# PCB_SIT210.net
KiCad netlist of a schematic drawn in EasyEDA
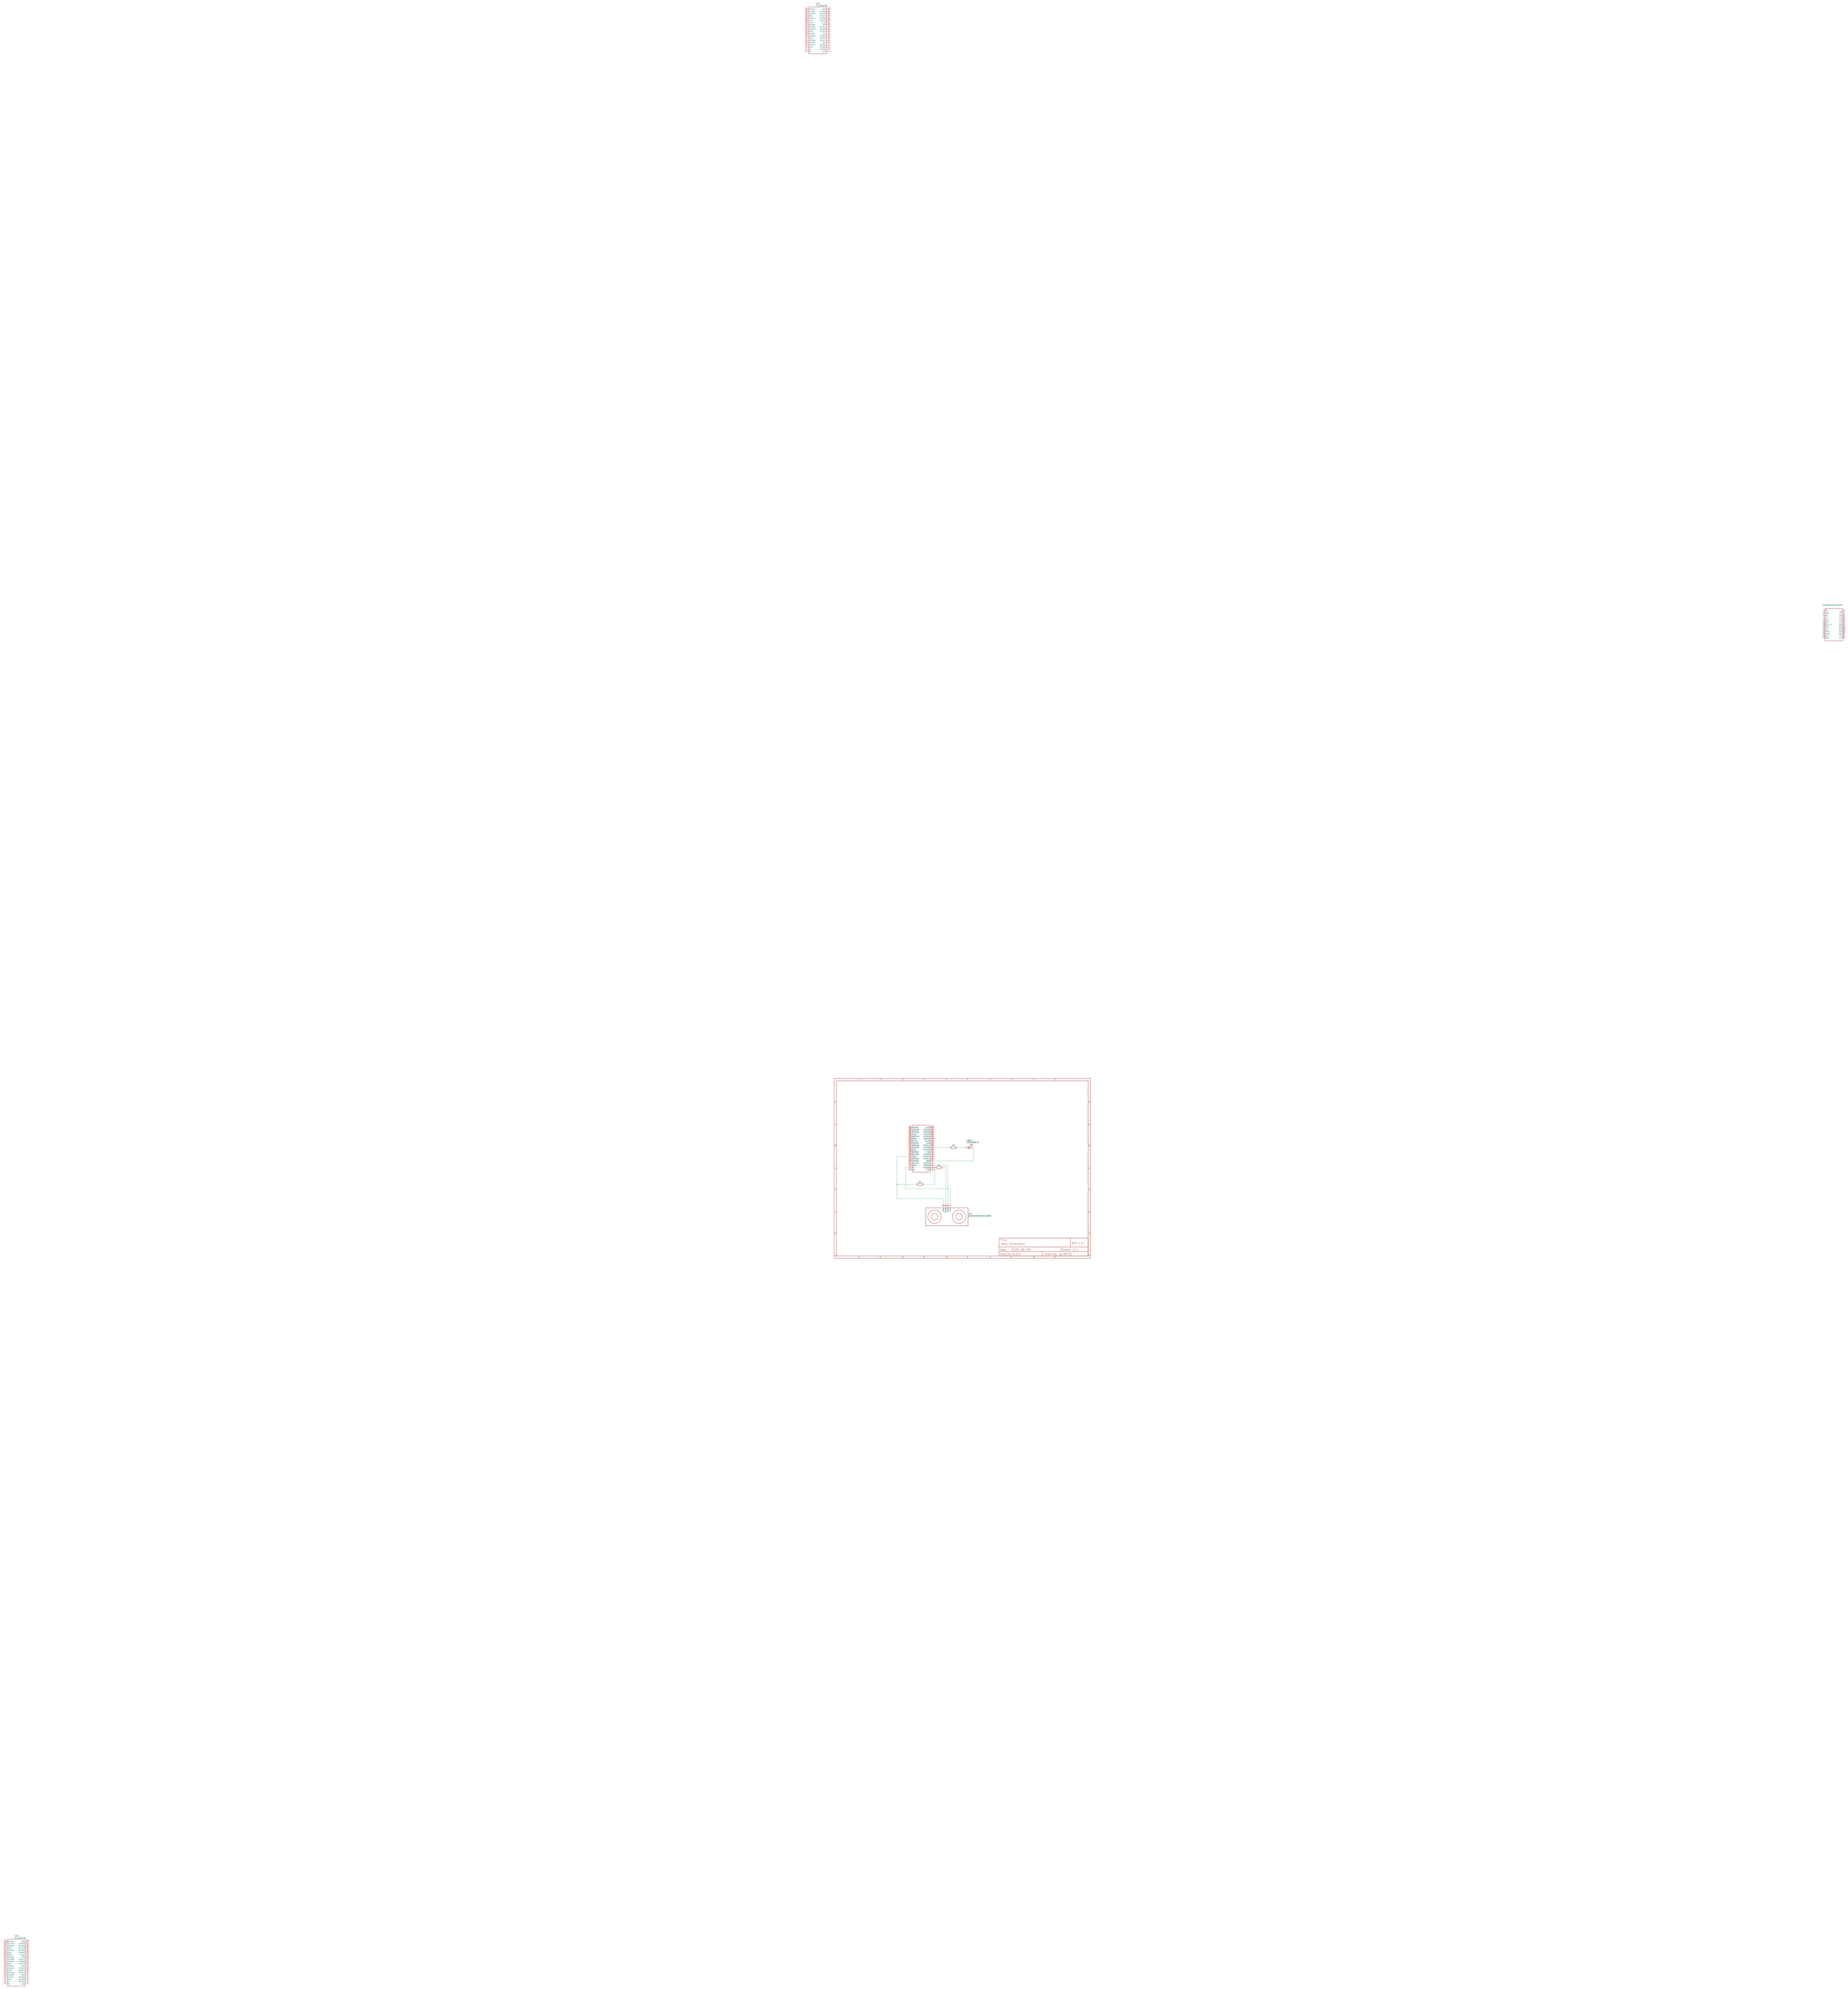
[diagram p0: schematic sheet]

(export (version "E")
  (design (tool "Eeschema 10.0.6"))
  (components
    (comp (ref "LED1")
      (value "LED-0603_R")
      (fields
        (field (name "BOM_Manufacturer Part") "19-217/R6C-AL1M2VY/3T")
        (field (name "BOM_Supplier Part") "C72044")
      )
      (libsource (lib "") (part "LED-0603_R"))
    )
    (comp (ref "R4") (value "1k") (libsource (lib "") (part "R_0201_EU")))
    (comp (ref "R5") (value "1k") (libsource (lib "") (part "R_0201_EU")))
    (comp (ref "R6") (value "1k") (libsource (lib "") (part "R_0201_EU")))
    (comp (ref "RASPBERRYPIGPIO")
      (value "Raspberry Pi")
      (fields (field (name "BOM_Manufacturer Part") "?"))
      (libsource (lib "") (part "Unknown_4485_-2105"))
    )
    (comp (ref "U1")
      (value "Pi connector")
      (fields (field (name "BOM_Manufacturer Part") "?"))
      (libsource (lib "") (part "Unknown_390_320"))
    )
    (comp (ref "U5")
      (value "ULTRASONIC-HC-SR04")
      (fields (field (name "BOM_Manufacturer Part") "?"))
      (libsource (lib "") (part "Unknown_410_580"))
    )
    (comp (ref "U23")
      (value "Pi connector")
      (fields (field (name "BOM_Manufacturer Part") "?"))
      (libsource (lib "") (part "Unknown_-3670_3970"))
    )
    (comp (ref "U24")
      (value "Pi connector")
      (fields (field (name "BOM_Manufacturer Part") "?"))
      (libsource (lib "") (part "Unknown_-75_-4695"))
    )
  )
  (nets
    (net (code "1") (name "Net-(LED1-Pad1)") (class "Default")
      (node (ref "LED1") (pin "1") (pinfunction "1_1") (pintype "unspecified"))
      (node (ref "R6") (pin "2") (pinfunction "2_2") (pintype "unspecified"))
    )
    (net (code "2") (name "Net-(LED1-Pad2)") (class "Default")
      (node (ref "LED1") (pin "2") (pinfunction "2_2") (pintype "unspecified"))
      (node (ref "U1") (pin "9") (pinfunction "GND_9") (pintype "unspecified"))
    )
    (net (code "3") (name "Net-(U1-GPIO02)") (class "Default")
      (node (ref "R4") (pin "1") (pinfunction "1_1") (pintype "unspecified"))
      (node (ref "R5") (pin "2") (pinfunction "2_2") (pintype "unspecified"))
      (node (ref "U1") (pin "1") (pinfunction "3.3v_1") (pintype "unspecified"))
      (node (ref "U1") (pin "3") (pinfunction "GPIO02_3") (pintype "unspecified"))
    )
    (net (code "4") (name "Net-(U1-GPIO03)") (class "Default")
      (node (ref "U1") (pin "5") (pinfunction "GPIO03_5") (pintype "unspecified"))
      (node (ref "U5") (pin "2") (pinfunction "TRIG_2") (pintype "output"))
    )
    (net (code "5") (name "Net-(U1-GPIO09)") (class "Default")
      (node (ref "R6") (pin "1") (pinfunction "1_1") (pintype "unspecified"))
      (node (ref "U1") (pin "21") (pinfunction "GPIO09_21") (pintype "unspecified"))
    )
    (net (code "6") (name "Net-(U5-ECHO)") (class "Default")
      (node (ref "R4") (pin "2") (pinfunction "2_2") (pintype "unspecified"))
      (node (ref "U5") (pin "3") (pinfunction "ECHO_3") (pintype "input"))
    )
    (net (code "7") (name "Net-(U5-GND)") (class "Default")
      (node (ref "R5") (pin "1") (pinfunction "1_1") (pintype "unspecified"))
      (node (ref "U1") (pin "14") (pinfunction "GND_14") (pintype "unspecified"))
      (node (ref "U5") (pin "4") (pinfunction "GND_4") (pintype "passive"))
    )
    (net (code "8") (name "Net-(U5-VCC)") (class "Default")
      (node (ref "U1") (pin "4") (pinfunction "5v_4") (pintype "unspecified"))
      (node (ref "U5") (pin "1") (pinfunction "VCC_1") (pintype "passive"))
    )
    (net (code "9") (name "unconnected-(RASPBERRYPIGPIO-#4-Pad7)") (class "Default")
      (node (ref "RASPBERRYPIGPIO") (pin "7") (pinfunction "#4_7") (pintype "unspecified"))
    )
    (net (code "10") (name "unconnected-(RASPBERRYPIGPIO-#17-Pad11)") (class "Default")
      (node (ref "RASPBERRYPIGPIO") (pin "11") (pinfunction "#17_11") (pintype "unspecified"))
    )
    (net (code "11") (name "unconnected-(RASPBERRYPIGPIO-#18-Pad12)") (class "Default")
      (node (ref "RASPBERRYPIGPIO") (pin "12") (pinfunction "#18_12") (pintype "unspecified"))
    )
    (net (code "12") (name "unconnected-(RASPBERRYPIGPIO-#21{slash}27-Pad13)") (class "Default")
      (node (ref "RASPBERRYPIGPIO") (pin "13") (pinfunction "#21/27_13") (pintype "unspecified"))
    )
    (net (code "13") (name "unconnected-(RASPBERRYPIGPIO-#22-Pad15)") (class "Default")
      (node (ref "RASPBERRYPIGPIO") (pin "15") (pinfunction "#22_15") (pintype "unspecified"))
    )
    (net (code "14") (name "unconnected-(RASPBERRYPIGPIO-#23-Pad16)") (class "Default")
      (node (ref "RASPBERRYPIGPIO") (pin "16") (pinfunction "#23_16") (pintype "unspecified"))
    )
    (net (code "15") (name "unconnected-(RASPBERRYPIGPIO-#24-Pad18)") (class "Default")
      (node (ref "RASPBERRYPIGPIO") (pin "18") (pinfunction "#24_18") (pintype "unspecified"))
    )
    (net (code "16") (name "unconnected-(RASPBERRYPIGPIO-#25-Pad22)") (class "Default")
      (node (ref "RASPBERRYPIGPIO") (pin "22") (pinfunction "#25_22") (pintype "unspecified"))
    )
    (net (code "17") (name "unconnected-(RASPBERRYPIGPIO-3v3-Pad1)") (class "Default")
      (node (ref "RASPBERRYPIGPIO") (pin "1") (pinfunction "3v3_1") (pintype "unspecified"))
    )
    (net (code "18") (name "unconnected-(RASPBERRYPIGPIO-3v3-Pad17)") (class "Default")
      (node (ref "RASPBERRYPIGPIO") (pin "17") (pinfunction "3v3_17") (pintype "unspecified"))
    )
    (net (code "19") (name "unconnected-(RASPBERRYPIGPIO-5v0-Pad2)") (class "Default")
      (node (ref "RASPBERRYPIGPIO") (pin "2") (pinfunction "5v0_2") (pintype "unspecified"))
    )
    (net (code "20") (name "unconnected-(RASPBERRYPIGPIO-5v0-Pad4)") (class "Default")
      (node (ref "RASPBERRYPIGPIO") (pin "4") (pinfunction "5v0_4") (pintype "unspecified"))
    )
    (net (code "21") (name "unconnected-(RASPBERRYPIGPIO-CE0-Pad24)") (class "Default")
      (node (ref "RASPBERRYPIGPIO") (pin "24") (pinfunction "CE0_24") (pintype "unspecified"))
    )
    (net (code "22") (name "unconnected-(RASPBERRYPIGPIO-CE1-Pad26)") (class "Default")
      (node (ref "RASPBERRYPIGPIO") (pin "26") (pinfunction "CE1_26") (pintype "unspecified"))
    )
    (net (code "23") (name "unconnected-(RASPBERRYPIGPIO-GND-Pad5)") (class "Default")
      (node (ref "RASPBERRYPIGPIO") (pin "5") (pinfunction "GND_5") (pintype "unspecified"))
    )
    (net (code "24") (name "unconnected-(RASPBERRYPIGPIO-GND-Pad6)") (class "Default")
      (node (ref "RASPBERRYPIGPIO") (pin "6") (pinfunction "GND_6") (pintype "unspecified"))
    )
    (net (code "25") (name "unconnected-(RASPBERRYPIGPIO-GND-Pad14)") (class "Default")
      (node (ref "RASPBERRYPIGPIO") (pin "14") (pinfunction "GND_14") (pintype "unspecified"))
    )
    (net (code "26") (name "unconnected-(RASPBERRYPIGPIO-GND-Pad20)") (class "Default")
      (node (ref "RASPBERRYPIGPIO") (pin "20") (pinfunction "GND_20") (pintype "unspecified"))
    )
    (net (code "27") (name "unconnected-(RASPBERRYPIGPIO-GND-Pad25)") (class "Default")
      (node (ref "RASPBERRYPIGPIO") (pin "25") (pinfunction "GND_25") (pintype "unspecified"))
    )
    (net (code "28") (name "unconnected-(RASPBERRYPIGPIO-MISO-Pad21)") (class "Default")
      (node (ref "RASPBERRYPIGPIO") (pin "21") (pinfunction "MISO_21") (pintype "unspecified"))
    )
    (net (code "29") (name "unconnected-(RASPBERRYPIGPIO-MOSI-Pad19)") (class "Default")
      (node (ref "RASPBERRYPIGPIO") (pin "19") (pinfunction "MOSI_19") (pintype "unspecified"))
    )
    (net (code "30") (name "unconnected-(RASPBERRYPIGPIO-RXD-Pad10)") (class "Default")
      (node (ref "RASPBERRYPIGPIO") (pin "10") (pinfunction "RXD_10") (pintype "unspecified"))
    )
    (net (code "31") (name "unconnected-(RASPBERRYPIGPIO-SCL-Pad5)") (class "Default")
      (node (ref "RASPBERRYPIGPIO") (pin "5") (pinfunction "SCL_5") (pintype "unspecified"))
    )
    (net (code "32") (name "unconnected-(RASPBERRYPIGPIO-SCLK-Pad23)") (class "Default")
      (node (ref "RASPBERRYPIGPIO") (pin "23") (pinfunction "SCLK_23") (pintype "unspecified"))
    )
    (net (code "33") (name "unconnected-(RASPBERRYPIGPIO-SDA-Pad3)") (class "Default")
      (node (ref "RASPBERRYPIGPIO") (pin "3") (pinfunction "SDA_3") (pintype "unspecified"))
    )
    (net (code "34") (name "unconnected-(RASPBERRYPIGPIO-TXD-Pad8)") (class "Default")
      (node (ref "RASPBERRYPIGPIO") (pin "8") (pinfunction "TXD_8") (pintype "unspecified"))
    )
    (net (code "35") (name "unconnected-(U1-3.3v-Pad17)") (class "Default")
      (node (ref "U1") (pin "17") (pinfunction "3.3v_17") (pintype "unspecified"))
    )
    (net (code "36") (name "unconnected-(U1-5v-Pad2)") (class "Default")
      (node (ref "U1") (pin "2") (pinfunction "5v_2") (pintype "unspecified"))
    )
    (net (code "37") (name "unconnected-(U1-GND-Pad6)") (class "Default")
      (node (ref "U1") (pin "6") (pinfunction "GND_6") (pintype "unspecified"))
    )
    (net (code "38") (name "unconnected-(U1-GND-Pad20)") (class "Default")
      (node (ref "U1") (pin "20") (pinfunction "GND_20") (pintype "unspecified"))
    )
    (net (code "39") (name "unconnected-(U1-GND-Pad25)") (class "Default")
      (node (ref "U1") (pin "25") (pinfunction "GND_25") (pintype "unspecified"))
    )
    (net (code "40") (name "unconnected-(U1-GND-Pad30)") (class "Default")
      (node (ref "U1") (pin "30") (pinfunction "GND_30") (pintype "unspecified"))
    )
    (net (code "41") (name "unconnected-(U1-GND-Pad34)") (class "Default")
      (node (ref "U1") (pin "34") (pinfunction "GND_34") (pintype "unspecified"))
    )
    (net (code "42") (name "unconnected-(U1-GND-Pad39)") (class "Default")
      (node (ref "U1") (pin "39") (pinfunction "GND_39") (pintype "unspecified"))
    )
    (net (code "43") (name "unconnected-(U1-GPIO04-Pad7)") (class "Default")
      (node (ref "U1") (pin "7") (pinfunction "GPIO04_7") (pintype "unspecified"))
    )
    (net (code "44") (name "unconnected-(U1-GPIO05-Pad29)") (class "Default")
      (node (ref "U1") (pin "29") (pinfunction "GPIO05_29") (pintype "unspecified"))
    )
    (net (code "45") (name "unconnected-(U1-GPIO06-Pad31)") (class "Default")
      (node (ref "U1") (pin "31") (pinfunction "GPIO06_31") (pintype "unspecified"))
    )
    (net (code "46") (name "unconnected-(U1-GPIO07-Pad26)") (class "Default")
      (node (ref "U1") (pin "26") (pinfunction "GPIO07_26") (pintype "unspecified"))
    )
    (net (code "47") (name "unconnected-(U1-GPIO08-Pad24)") (class "Default")
      (node (ref "U1") (pin "24") (pinfunction "GPIO08_24") (pintype "unspecified"))
    )
    (net (code "48") (name "unconnected-(U1-GPIO10-Pad19)") (class "Default")
      (node (ref "U1") (pin "19") (pinfunction "GPIO10_19") (pintype "unspecified"))
    )
    (net (code "49") (name "unconnected-(U1-GPIO11-Pad23)") (class "Default")
      (node (ref "U1") (pin "23") (pinfunction "GPIO11_23") (pintype "unspecified"))
    )
    (net (code "50") (name "unconnected-(U1-GPIO12-Pad32)") (class "Default")
      (node (ref "U1") (pin "32") (pinfunction "GPIO12_32") (pintype "unspecified"))
    )
    (net (code "51") (name "unconnected-(U1-GPIO13-Pad33)") (class "Default")
      (node (ref "U1") (pin "33") (pinfunction "GPIO13_33") (pintype "unspecified"))
    )
    (net (code "52") (name "unconnected-(U1-GPIO14-Pad8)") (class "Default")
      (node (ref "U1") (pin "8") (pinfunction "GPIO14_8") (pintype "unspecified"))
    )
    (net (code "53") (name "unconnected-(U1-GPIO15-Pad10)") (class "Default")
      (node (ref "U1") (pin "10") (pinfunction "GPIO15_10") (pintype "unspecified"))
    )
    (net (code "54") (name "unconnected-(U1-GPIO16-Pad36)") (class "Default")
      (node (ref "U1") (pin "36") (pinfunction "GPIO16_36") (pintype "unspecified"))
    )
    (net (code "55") (name "unconnected-(U1-GPIO17-Pad11)") (class "Default")
      (node (ref "U1") (pin "11") (pinfunction "GPIO17_11") (pintype "unspecified"))
    )
    (net (code "56") (name "unconnected-(U1-GPIO18-Pad12)") (class "Default")
      (node (ref "U1") (pin "12") (pinfunction "GPIO18_12") (pintype "unspecified"))
    )
    (net (code "57") (name "unconnected-(U1-GPIO19-Pad35)") (class "Default")
      (node (ref "U1") (pin "35") (pinfunction "GPIO19_35") (pintype "unspecified"))
    )
    (net (code "58") (name "unconnected-(U1-GPIO20-Pad38)") (class "Default")
      (node (ref "U1") (pin "38") (pinfunction "GPIO20_38") (pintype "unspecified"))
    )
    (net (code "59") (name "unconnected-(U1-GPIO21-Pad40)") (class "Default")
      (node (ref "U1") (pin "40") (pinfunction "GPIO21_40") (pintype "unspecified"))
    )
    (net (code "60") (name "unconnected-(U1-GPIO22-Pad15)") (class "Default")
      (node (ref "U1") (pin "15") (pinfunction "GPIO22_15") (pintype "unspecified"))
    )
    (net (code "61") (name "unconnected-(U1-GPIO23-Pad16)") (class "Default")
      (node (ref "U1") (pin "16") (pinfunction "GPIO23_16") (pintype "unspecified"))
    )
    (net (code "62") (name "unconnected-(U1-GPIO24-Pad18)") (class "Default")
      (node (ref "U1") (pin "18") (pinfunction "GPIO24_18") (pintype "unspecified"))
    )
    (net (code "63") (name "unconnected-(U1-GPIO25-Pad22)") (class "Default")
      (node (ref "U1") (pin "22") (pinfunction "GPIO25_22") (pintype "unspecified"))
    )
    (net (code "64") (name "unconnected-(U1-GPIO26-Pad37)") (class "Default")
      (node (ref "U1") (pin "37") (pinfunction "GPIO26_37") (pintype "unspecified"))
    )
    (net (code "65") (name "unconnected-(U1-GPIO27-Pad13)") (class "Default")
      (node (ref "U1") (pin "13") (pinfunction "GPIO27_13") (pintype "unspecified"))
    )
    (net (code "66") (name "unconnected-(U1-ID_SC-Pad28)") (class "Default")
      (node (ref "U1") (pin "28") (pinfunction "ID_SC_28") (pintype "unspecified"))
    )
    (net (code "67") (name "unconnected-(U1-ID_SD-Pad27)") (class "Default")
      (node (ref "U1") (pin "27") (pinfunction "ID_SD_27") (pintype "unspecified"))
    )
    (net (code "68") (name "unconnected-(U23-3.3v-Pad1)") (class "Default")
      (node (ref "U23") (pin "1") (pinfunction "3.3v_1") (pintype "unspecified"))
    )
    (net (code "69") (name "unconnected-(U23-3.3v-Pad17)") (class "Default")
      (node (ref "U23") (pin "17") (pinfunction "3.3v_17") (pintype "unspecified"))
    )
    (net (code "70") (name "unconnected-(U23-5v-Pad2)") (class "Default")
      (node (ref "U23") (pin "2") (pinfunction "5v_2") (pintype "unspecified"))
    )
    (net (code "71") (name "unconnected-(U23-5v-Pad4)") (class "Default")
      (node (ref "U23") (pin "4") (pinfunction "5v_4") (pintype "unspecified"))
    )
    (net (code "72") (name "unconnected-(U23-GND-Pad6)") (class "Default")
      (node (ref "U23") (pin "6") (pinfunction "GND_6") (pintype "unspecified"))
    )
    (net (code "73") (name "unconnected-(U23-GND-Pad9)") (class "Default")
      (node (ref "U23") (pin "9") (pinfunction "GND_9") (pintype "unspecified"))
    )
    (net (code "74") (name "unconnected-(U23-GND-Pad14)") (class "Default")
      (node (ref "U23") (pin "14") (pinfunction "GND_14") (pintype "unspecified"))
    )
    (net (code "75") (name "unconnected-(U23-GND-Pad20)") (class "Default")
      (node (ref "U23") (pin "20") (pinfunction "GND_20") (pintype "unspecified"))
    )
    (net (code "76") (name "unconnected-(U23-GND-Pad25)") (class "Default")
      (node (ref "U23") (pin "25") (pinfunction "GND_25") (pintype "unspecified"))
    )
    (net (code "77") (name "unconnected-(U23-GND-Pad30)") (class "Default")
      (node (ref "U23") (pin "30") (pinfunction "GND_30") (pintype "unspecified"))
    )
    (net (code "78") (name "unconnected-(U23-GND-Pad34)") (class "Default")
      (node (ref "U23") (pin "34") (pinfunction "GND_34") (pintype "unspecified"))
    )
    (net (code "79") (name "unconnected-(U23-GND-Pad39)") (class "Default")
      (node (ref "U23") (pin "39") (pinfunction "GND_39") (pintype "unspecified"))
    )
    (net (code "80") (name "unconnected-(U23-GPIO02-Pad3)") (class "Default")
      (node (ref "U23") (pin "3") (pinfunction "GPIO02_3") (pintype "unspecified"))
    )
    (net (code "81") (name "unconnected-(U23-GPIO03-Pad5)") (class "Default")
      (node (ref "U23") (pin "5") (pinfunction "GPIO03_5") (pintype "unspecified"))
    )
    (net (code "82") (name "unconnected-(U23-GPIO04-Pad7)") (class "Default")
      (node (ref "U23") (pin "7") (pinfunction "GPIO04_7") (pintype "unspecified"))
    )
    (net (code "83") (name "unconnected-(U23-GPIO05-Pad29)") (class "Default")
      (node (ref "U23") (pin "29") (pinfunction "GPIO05_29") (pintype "unspecified"))
    )
    (net (code "84") (name "unconnected-(U23-GPIO06-Pad31)") (class "Default")
      (node (ref "U23") (pin "31") (pinfunction "GPIO06_31") (pintype "unspecified"))
    )
    (net (code "85") (name "unconnected-(U23-GPIO07-Pad26)") (class "Default")
      (node (ref "U23") (pin "26") (pinfunction "GPIO07_26") (pintype "unspecified"))
    )
    (net (code "86") (name "unconnected-(U23-GPIO08-Pad24)") (class "Default")
      (node (ref "U23") (pin "24") (pinfunction "GPIO08_24") (pintype "unspecified"))
    )
    (net (code "87") (name "unconnected-(U23-GPIO09-Pad21)") (class "Default")
      (node (ref "U23") (pin "21") (pinfunction "GPIO09_21") (pintype "unspecified"))
    )
    (net (code "88") (name "unconnected-(U23-GPIO10-Pad19)") (class "Default")
      (node (ref "U23") (pin "19") (pinfunction "GPIO10_19") (pintype "unspecified"))
    )
    (net (code "89") (name "unconnected-(U23-GPIO11-Pad23)") (class "Default")
      (node (ref "U23") (pin "23") (pinfunction "GPIO11_23") (pintype "unspecified"))
    )
    (net (code "90") (name "unconnected-(U23-GPIO12-Pad32)") (class "Default")
      (node (ref "U23") (pin "32") (pinfunction "GPIO12_32") (pintype "unspecified"))
    )
    (net (code "91") (name "unconnected-(U23-GPIO13-Pad33)") (class "Default")
      (node (ref "U23") (pin "33") (pinfunction "GPIO13_33") (pintype "unspecified"))
    )
    (net (code "92") (name "unconnected-(U23-GPIO14-Pad8)") (class "Default")
      (node (ref "U23") (pin "8") (pinfunction "GPIO14_8") (pintype "unspecified"))
    )
    (net (code "93") (name "unconnected-(U23-GPIO15-Pad10)") (class "Default")
      (node (ref "U23") (pin "10") (pinfunction "GPIO15_10") (pintype "unspecified"))
    )
    (net (code "94") (name "unconnected-(U23-GPIO16-Pad36)") (class "Default")
      (node (ref "U23") (pin "36") (pinfunction "GPIO16_36") (pintype "unspecified"))
    )
    (net (code "95") (name "unconnected-(U23-GPIO17-Pad11)") (class "Default")
      (node (ref "U23") (pin "11") (pinfunction "GPIO17_11") (pintype "unspecified"))
    )
    (net (code "96") (name "unconnected-(U23-GPIO18-Pad12)") (class "Default")
      (node (ref "U23") (pin "12") (pinfunction "GPIO18_12") (pintype "unspecified"))
    )
    (net (code "97") (name "unconnected-(U23-GPIO19-Pad35)") (class "Default")
      (node (ref "U23") (pin "35") (pinfunction "GPIO19_35") (pintype "unspecified"))
    )
    (net (code "98") (name "unconnected-(U23-GPIO20-Pad38)") (class "Default")
      (node (ref "U23") (pin "38") (pinfunction "GPIO20_38") (pintype "unspecified"))
    )
    (net (code "99") (name "unconnected-(U23-GPIO21-Pad40)") (class "Default")
      (node (ref "U23") (pin "40") (pinfunction "GPIO21_40") (pintype "unspecified"))
    )
    (net (code "100") (name "unconnected-(U23-GPIO22-Pad15)") (class "Default")
      (node (ref "U23") (pin "15") (pinfunction "GPIO22_15") (pintype "unspecified"))
    )
    (net (code "101") (name "unconnected-(U23-GPIO23-Pad16)") (class "Default")
      (node (ref "U23") (pin "16") (pinfunction "GPIO23_16") (pintype "unspecified"))
    )
    (net (code "102") (name "unconnected-(U23-GPIO24-Pad18)") (class "Default")
      (node (ref "U23") (pin "18") (pinfunction "GPIO24_18") (pintype "unspecified"))
    )
    (net (code "103") (name "unconnected-(U23-GPIO25-Pad22)") (class "Default")
      (node (ref "U23") (pin "22") (pinfunction "GPIO25_22") (pintype "unspecified"))
    )
    (net (code "104") (name "unconnected-(U23-GPIO26-Pad37)") (class "Default")
      (node (ref "U23") (pin "37") (pinfunction "GPIO26_37") (pintype "unspecified"))
    )
    (net (code "105") (name "unconnected-(U23-GPIO27-Pad13)") (class "Default")
      (node (ref "U23") (pin "13") (pinfunction "GPIO27_13") (pintype "unspecified"))
    )
    (net (code "106") (name "unconnected-(U23-ID_SC-Pad28)") (class "Default")
      (node (ref "U23") (pin "28") (pinfunction "ID_SC_28") (pintype "unspecified"))
    )
    (net (code "107") (name "unconnected-(U23-ID_SD-Pad27)") (class "Default")
      (node (ref "U23") (pin "27") (pinfunction "ID_SD_27") (pintype "unspecified"))
    )
    (net (code "108") (name "unconnected-(U24-3.3v-Pad1)") (class "Default")
      (node (ref "U24") (pin "1") (pinfunction "3.3v_1") (pintype "unspecified"))
    )
    (net (code "109") (name "unconnected-(U24-3.3v-Pad17)") (class "Default")
      (node (ref "U24") (pin "17") (pinfunction "3.3v_17") (pintype "unspecified"))
    )
    (net (code "110") (name "unconnected-(U24-5v-Pad2)") (class "Default")
      (node (ref "U24") (pin "2") (pinfunction "5v_2") (pintype "unspecified"))
    )
    (net (code "111") (name "unconnected-(U24-5v-Pad4)") (class "Default")
      (node (ref "U24") (pin "4") (pinfunction "5v_4") (pintype "unspecified"))
    )
    (net (code "112") (name "unconnected-(U24-GND-Pad6)") (class "Default")
      (node (ref "U24") (pin "6") (pinfunction "GND_6") (pintype "unspecified"))
    )
    (net (code "113") (name "unconnected-(U24-GND-Pad9)") (class "Default")
      (node (ref "U24") (pin "9") (pinfunction "GND_9") (pintype "unspecified"))
    )
    (net (code "114") (name "unconnected-(U24-GND-Pad14)") (class "Default")
      (node (ref "U24") (pin "14") (pinfunction "GND_14") (pintype "unspecified"))
    )
    (net (code "115") (name "unconnected-(U24-GND-Pad20)") (class "Default")
      (node (ref "U24") (pin "20") (pinfunction "GND_20") (pintype "unspecified"))
    )
    (net (code "116") (name "unconnected-(U24-GND-Pad25)") (class "Default")
      (node (ref "U24") (pin "25") (pinfunction "GND_25") (pintype "unspecified"))
    )
    (net (code "117") (name "unconnected-(U24-GND-Pad30)") (class "Default")
      (node (ref "U24") (pin "30") (pinfunction "GND_30") (pintype "unspecified"))
    )
    (net (code "118") (name "unconnected-(U24-GND-Pad34)") (class "Default")
      (node (ref "U24") (pin "34") (pinfunction "GND_34") (pintype "unspecified"))
    )
    (net (code "119") (name "unconnected-(U24-GND-Pad39)") (class "Default")
      (node (ref "U24") (pin "39") (pinfunction "GND_39") (pintype "unspecified"))
    )
    (net (code "120") (name "unconnected-(U24-GPIO02-Pad3)") (class "Default")
      (node (ref "U24") (pin "3") (pinfunction "GPIO02_3") (pintype "unspecified"))
    )
    (net (code "121") (name "unconnected-(U24-GPIO03-Pad5)") (class "Default")
      (node (ref "U24") (pin "5") (pinfunction "GPIO03_5") (pintype "unspecified"))
    )
    (net (code "122") (name "unconnected-(U24-GPIO04-Pad7)") (class "Default")
      (node (ref "U24") (pin "7") (pinfunction "GPIO04_7") (pintype "unspecified"))
    )
    (net (code "123") (name "unconnected-(U24-GPIO05-Pad29)") (class "Default")
      (node (ref "U24") (pin "29") (pinfunction "GPIO05_29") (pintype "unspecified"))
    )
    (net (code "124") (name "unconnected-(U24-GPIO06-Pad31)") (class "Default")
      (node (ref "U24") (pin "31") (pinfunction "GPIO06_31") (pintype "unspecified"))
    )
    (net (code "125") (name "unconnected-(U24-GPIO07-Pad26)") (class "Default")
      (node (ref "U24") (pin "26") (pinfunction "GPIO07_26") (pintype "unspecified"))
    )
    (net (code "126") (name "unconnected-(U24-GPIO08-Pad24)") (class "Default")
      (node (ref "U24") (pin "24") (pinfunction "GPIO08_24") (pintype "unspecified"))
    )
    (net (code "127") (name "unconnected-(U24-GPIO09-Pad21)") (class "Default")
      (node (ref "U24") (pin "21") (pinfunction "GPIO09_21") (pintype "unspecified"))
    )
    (net (code "128") (name "unconnected-(U24-GPIO10-Pad19)") (class "Default")
      (node (ref "U24") (pin "19") (pinfunction "GPIO10_19") (pintype "unspecified"))
    )
    (net (code "129") (name "unconnected-(U24-GPIO11-Pad23)") (class "Default")
      (node (ref "U24") (pin "23") (pinfunction "GPIO11_23") (pintype "unspecified"))
    )
    (net (code "130") (name "unconnected-(U24-GPIO12-Pad32)") (class "Default")
      (node (ref "U24") (pin "32") (pinfunction "GPIO12_32") (pintype "unspecified"))
    )
    (net (code "131") (name "unconnected-(U24-GPIO13-Pad33)") (class "Default")
      (node (ref "U24") (pin "33") (pinfunction "GPIO13_33") (pintype "unspecified"))
    )
    (net (code "132") (name "unconnected-(U24-GPIO14-Pad8)") (class "Default")
      (node (ref "U24") (pin "8") (pinfunction "GPIO14_8") (pintype "unspecified"))
    )
    (net (code "133") (name "unconnected-(U24-GPIO15-Pad10)") (class "Default")
      (node (ref "U24") (pin "10") (pinfunction "GPIO15_10") (pintype "unspecified"))
    )
    (net (code "134") (name "unconnected-(U24-GPIO16-Pad36)") (class "Default")
      (node (ref "U24") (pin "36") (pinfunction "GPIO16_36") (pintype "unspecified"))
    )
    (net (code "135") (name "unconnected-(U24-GPIO17-Pad11)") (class "Default")
      (node (ref "U24") (pin "11") (pinfunction "GPIO17_11") (pintype "unspecified"))
    )
    (net (code "136") (name "unconnected-(U24-GPIO18-Pad12)") (class "Default")
      (node (ref "U24") (pin "12") (pinfunction "GPIO18_12") (pintype "unspecified"))
    )
    (net (code "137") (name "unconnected-(U24-GPIO19-Pad35)") (class "Default")
      (node (ref "U24") (pin "35") (pinfunction "GPIO19_35") (pintype "unspecified"))
    )
    (net (code "138") (name "unconnected-(U24-GPIO20-Pad38)") (class "Default")
      (node (ref "U24") (pin "38") (pinfunction "GPIO20_38") (pintype "unspecified"))
    )
    (net (code "139") (name "unconnected-(U24-GPIO21-Pad40)") (class "Default")
      (node (ref "U24") (pin "40") (pinfunction "GPIO21_40") (pintype "unspecified"))
    )
    (net (code "140") (name "unconnected-(U24-GPIO22-Pad15)") (class "Default")
      (node (ref "U24") (pin "15") (pinfunction "GPIO22_15") (pintype "unspecified"))
    )
    (net (code "141") (name "unconnected-(U24-GPIO23-Pad16)") (class "Default")
      (node (ref "U24") (pin "16") (pinfunction "GPIO23_16") (pintype "unspecified"))
    )
    (net (code "142") (name "unconnected-(U24-GPIO24-Pad18)") (class "Default")
      (node (ref "U24") (pin "18") (pinfunction "GPIO24_18") (pintype "unspecified"))
    )
    (net (code "143") (name "unconnected-(U24-GPIO25-Pad22)") (class "Default")
      (node (ref "U24") (pin "22") (pinfunction "GPIO25_22") (pintype "unspecified"))
    )
    (net (code "144") (name "unconnected-(U24-GPIO26-Pad37)") (class "Default")
      (node (ref "U24") (pin "37") (pinfunction "GPIO26_37") (pintype "unspecified"))
    )
    (net (code "145") (name "unconnected-(U24-GPIO27-Pad13)") (class "Default")
      (node (ref "U24") (pin "13") (pinfunction "GPIO27_13") (pintype "unspecified"))
    )
    (net (code "146") (name "unconnected-(U24-ID_SC-Pad28)") (class "Default")
      (node (ref "U24") (pin "28") (pinfunction "ID_SC_28") (pintype "unspecified"))
    )
    (net (code "147") (name "unconnected-(U24-ID_SD-Pad27)") (class "Default")
      (node (ref "U24") (pin "27") (pinfunction "ID_SD_27") (pintype "unspecified"))
    )
  )
)
